# Condor2a_Current_Sensor.net
KiCad netlist of a schematic drawn in Altium Designer
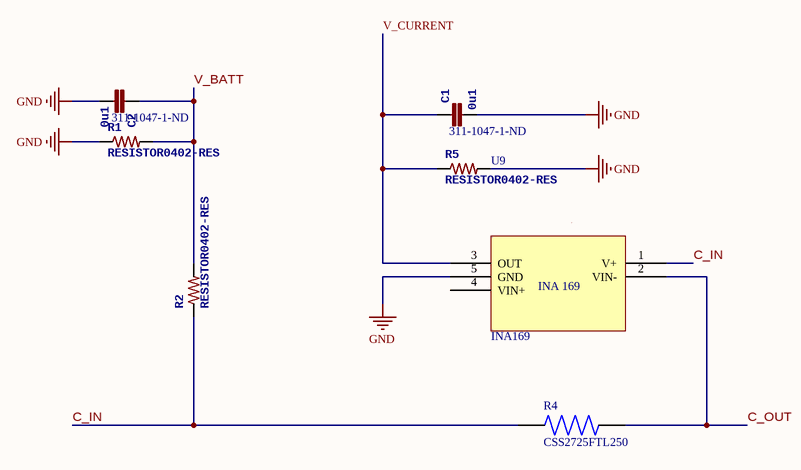
[diagram p0: Condor2a_Current_Sensor.SchDoc]

(export (version "E")
  (design (tool "Eeschema 10.0.6"))
  (components
    (comp (ref "C1")
      (value "0u1")
      (footprint "0402-CAP")
      (fields
        (field (name "PARTNO") "CC0402ZRY5V7BB104")
        (field (name "SUPPLIER PART NUMBER 1") "311-1047-1-ND")
      )
      (libsource (lib "") (part "CAP0402_1"))
    )
    (comp (ref "C2")
      (value "0u1")
      (footprint "0402-CAP")
      (fields
        (field (name "PARTNO") "CC0402ZRY5V7BB104")
        (field (name "SUPPLIER PART NUMBER 1") "311-1047-1-ND")
      )
      (libsource (lib "CB_REV_C") (part "CAP0402"))
    )
    (comp (ref "R1")
      (value "RESISTOR0402-RES")
      (footprint "0402-RES")
      (libsource (lib "CB_REV_C") (part "RESISTOR0402-RES"))
    )
    (comp (ref "R2")
      (value "RESISTOR0402-RES")
      (footprint "0402-RES")
      (libsource (lib "CB_REV_C") (part "RESISTOR0402-RES"))
    )
    (comp (ref "R4")
      (value "CSS2725FTL250")
      (footprint "RESC6864X124N")
      (description "250 ÂµOhms Â±1% 4W Chip Resistor Nonstandard Automotive AEC-Q200, Current Sense Metal Element")
      (fields
        (field (name "MF") "Stackpole Electronics Inc")
        (field (name "DIGI-KEY_PART_NUMBER") "CSS2725FTL250CT-ND")
      )
      (libsource (lib "CB_REV_C") (part "CSS2725FTL250"))
    )
    (comp (ref "R5")
      (value "RESISTOR0402-RES")
      (footprint "0402-RES")
      (libsource (lib "CB_REV_C") (part "RESISTOR0402-RES"))
    )
    (comp (ref "U9") (value "INA169") (footprint "INA169") (libsource (lib "CB_REV_C") (part "INA169")))
  )
  (nets
    (net (code "1") (name "/C_IN") (class "Default")
      (node (ref "R2") (pin "P1") (pinfunction "1_P1") (pintype "passive"))
      (node (ref "R4") (pin "1") (pinfunction "1_1") (pintype "passive"))
      (node (ref "U9") (pin "1") (pinfunction "V+_1") (pintype "passive"))
    )
    (net (code "2") (name "/C_OUT") (class "Default")
      (node (ref "R4") (pin "2") (pinfunction "2_2") (pintype "passive"))
      (node (ref "U9") (pin "2") (pinfunction "VIN-_2") (pintype "passive"))
    )
    (net (code "3") (name "/V_BATT") (class "Default")
      (node (ref "C2") (pin "P$2") (pinfunction "2_P$2") (pintype "passive"))
      (node (ref "R1") (pin "P2") (pinfunction "2_P2") (pintype "passive"))
      (node (ref "R2") (pin "P2") (pinfunction "2_P2") (pintype "passive"))
    )
    (net (code "4") (name "/V_CURRENT") (class "Default")
      (node (ref "C1") (pin "P$2") (pinfunction "2_P$2") (pintype "passive"))
      (node (ref "R5") (pin "P1") (pinfunction "1_P1") (pintype "passive"))
      (node (ref "U9") (pin "3") (pinfunction "OUT_3") (pintype "passive"))
    )
    (net (code "5") (name "GND") (class "Default")
      (node (ref "C1") (pin "P$1") (pinfunction "1_P$1") (pintype "passive"))
      (node (ref "C2") (pin "P$1") (pinfunction "1_P$1") (pintype "passive"))
      (node (ref "R1") (pin "P1") (pinfunction "1_P1") (pintype "passive"))
      (node (ref "R5") (pin "P2") (pinfunction "2_P2") (pintype "passive"))
      (node (ref "U9") (pin "5") (pinfunction "GND_5") (pintype "passive"))
    )
    (net (code "6") (name "unconnected-(U9-VIN+-Pad4)") (class "Default")
      (node (ref "U9") (pin "4") (pinfunction "VIN+_4") (pintype "passive"))
    )
  )
)
